# Badge.net
KiCad netlist of a schematic drawn in Altium Designer
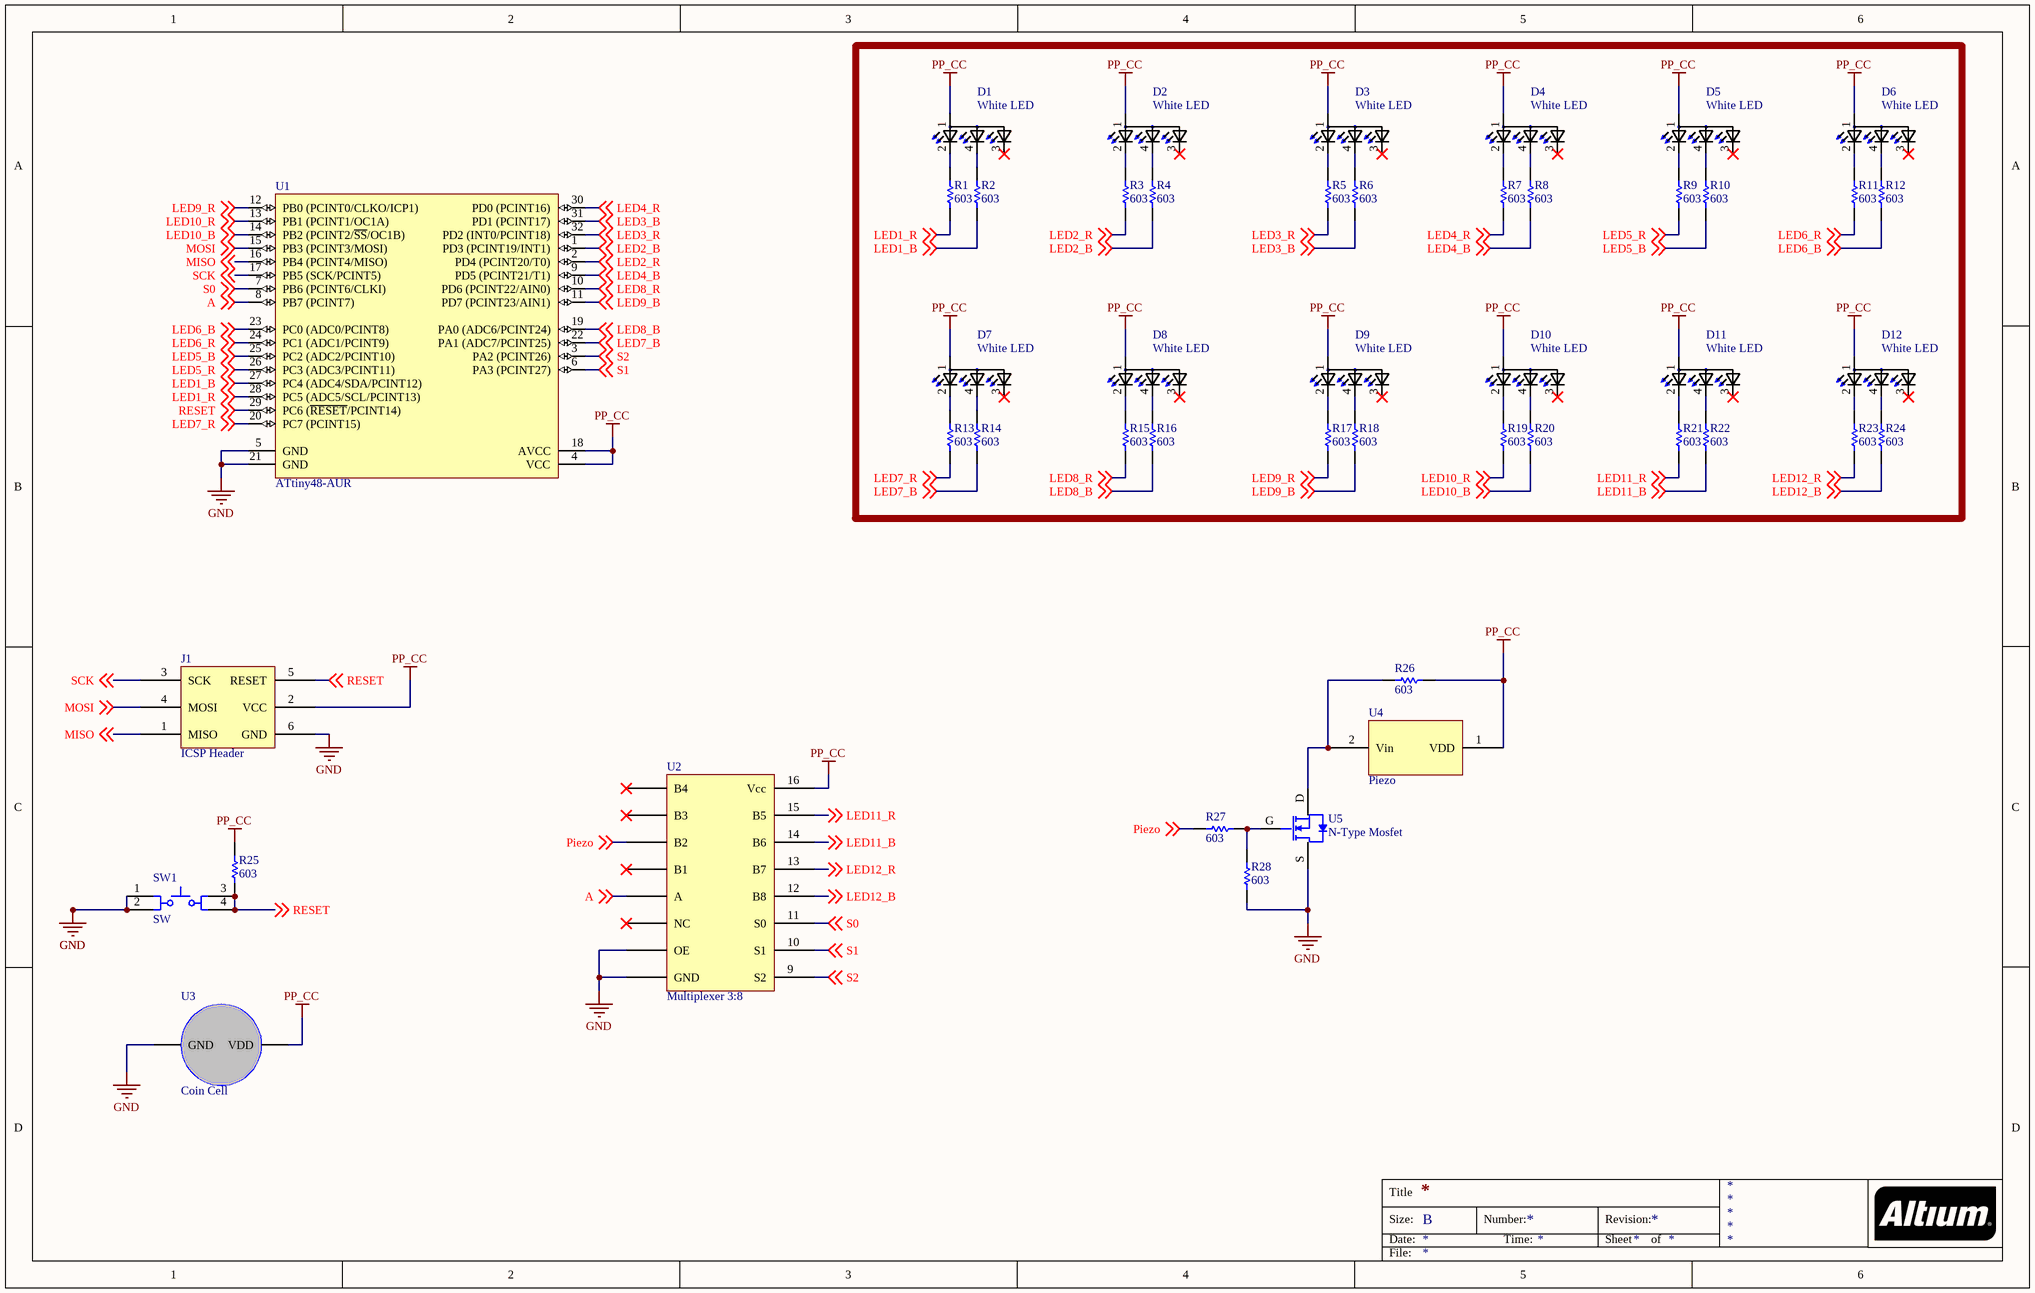
[diagram p0: Badge.SchDoc]

(export (version "E")
  (design (tool "Eeschema 10.0.6"))
  (components
    (comp (ref "D1")
      (value "White LED")
      (footprint "*LED_ASMB-KTF0-0A306")
      (description "2220 Tricolor PLCC4 Surface Mount LED")
      (fields (field (name "MF") "Broadcom Limited") (field (name "DIGI-KEY_PART_NUMBER") "516-3906-1-ND"))
      (libsource (lib "badge") (part "ASMB-KTF0-0A306"))
    )
    (comp (ref "D2")
      (value "White LED")
      (footprint "*LED_ASMB-KTF0-0A306")
      (description "2220 Tricolor PLCC4 Surface Mount LED")
      (fields (field (name "MF") "Broadcom Limited") (field (name "DIGI-KEY_PART_NUMBER") "516-3906-1-ND"))
      (libsource (lib "badge") (part "ASMB-KTF0-0A306"))
    )
    (comp (ref "D3")
      (value "White LED")
      (footprint "*LED_ASMB-KTF0-0A306")
      (description "2220 Tricolor PLCC4 Surface Mount LED")
      (fields (field (name "MF") "Broadcom Limited") (field (name "DIGI-KEY_PART_NUMBER") "516-3906-1-ND"))
      (libsource (lib "badge") (part "ASMB-KTF0-0A306"))
    )
    (comp (ref "D4")
      (value "White LED")
      (footprint "*LED_ASMB-KTF0-0A306")
      (description "2220 Tricolor PLCC4 Surface Mount LED")
      (fields (field (name "MF") "Broadcom Limited") (field (name "DIGI-KEY_PART_NUMBER") "516-3906-1-ND"))
      (libsource (lib "badge") (part "ASMB-KTF0-0A306"))
    )
    (comp (ref "D5")
      (value "White LED")
      (footprint "*LED_ASMB-KTF0-0A306")
      (description "2220 Tricolor PLCC4 Surface Mount LED")
      (fields (field (name "MF") "Broadcom Limited") (field (name "DIGI-KEY_PART_NUMBER") "516-3906-1-ND"))
      (libsource (lib "badge") (part "ASMB-KTF0-0A306"))
    )
    (comp (ref "D6")
      (value "White LED")
      (footprint "*LED_ASMB-KTF0-0A306")
      (description "2220 Tricolor PLCC4 Surface Mount LED")
      (fields (field (name "MF") "Broadcom Limited") (field (name "DIGI-KEY_PART_NUMBER") "516-3906-1-ND"))
      (libsource (lib "badge") (part "ASMB-KTF0-0A306"))
    )
    (comp (ref "D7")
      (value "White LED")
      (footprint "*LED_ASMB-KTF0-0A306")
      (description "2220 Tricolor PLCC4 Surface Mount LED")
      (fields (field (name "MF") "Broadcom Limited") (field (name "DIGI-KEY_PART_NUMBER") "516-3906-1-ND"))
      (libsource (lib "badge") (part "ASMB-KTF0-0A306"))
    )
    (comp (ref "D8")
      (value "White LED")
      (footprint "*LED_ASMB-KTF0-0A306")
      (description "2220 Tricolor PLCC4 Surface Mount LED")
      (fields (field (name "MF") "Broadcom Limited") (field (name "DIGI-KEY_PART_NUMBER") "516-3906-1-ND"))
      (libsource (lib "badge") (part "ASMB-KTF0-0A306"))
    )
    (comp (ref "D9")
      (value "White LED")
      (footprint "*LED_ASMB-KTF0-0A306")
      (description "2220 Tricolor PLCC4 Surface Mount LED")
      (fields (field (name "MF") "Broadcom Limited") (field (name "DIGI-KEY_PART_NUMBER") "516-3906-1-ND"))
      (libsource (lib "badge") (part "ASMB-KTF0-0A306"))
    )
    (comp (ref "D10")
      (value "White LED")
      (footprint "*LED_ASMB-KTF0-0A306")
      (description "2220 Tricolor PLCC4 Surface Mount LED")
      (fields (field (name "MF") "Broadcom Limited") (field (name "DIGI-KEY_PART_NUMBER") "516-3906-1-ND"))
      (libsource (lib "badge") (part "ASMB-KTF0-0A306"))
    )
    (comp (ref "D11")
      (value "White LED")
      (footprint "*LED_ASMB-KTF0-0A306")
      (description "2220 Tricolor PLCC4 Surface Mount LED")
      (fields (field (name "MF") "Broadcom Limited") (field (name "DIGI-KEY_PART_NUMBER") "516-3906-1-ND"))
      (libsource (lib "badge") (part "ASMB-KTF0-0A306"))
    )
    (comp (ref "D12")
      (value "White LED")
      (footprint "*LED_ASMB-KTF0-0A306")
      (description "2220 Tricolor PLCC4 Surface Mount LED")
      (fields (field (name "MF") "Broadcom Limited") (field (name "DIGI-KEY_PART_NUMBER") "516-3906-1-ND"))
      (libsource (lib "badge") (part "ASMB-KTF0-0A306"))
    )
    (comp (ref "J1")
      (value "ICSP Header")
      (footprint "programmer header")
      (libsource (lib "badge") (part "ICSP Header"))
    )
    (comp (ref "R1")
      (value "603")
      (footprint "RESC0603(1608)_L")
      (description "330R 0.1W 5% 0603 (1608 Metric)  SMD")
      (fields (field (name "TOLERANCE") "5 %") (field (name "POWER") "0.1 W"))
      (libsource (lib "Altium Content Vault") (part "RES"))
    )
    (comp (ref "R2")
      (value "603")
      (footprint "RESC0603(1608)_L")
      (description "330R 0.1W 5% 0603 (1608 Metric)  SMD")
      (fields (field (name "TOLERANCE") "5 %") (field (name "POWER") "0.1 W"))
      (libsource (lib "Altium Content Vault") (part "RES"))
    )
    (comp (ref "R3")
      (value "603")
      (footprint "RESC0603(1608)_L")
      (description "330R 0.1W 5% 0603 (1608 Metric)  SMD")
      (fields (field (name "TOLERANCE") "5 %") (field (name "POWER") "0.1 W"))
      (libsource (lib "Altium Content Vault") (part "RES"))
    )
    (comp (ref "R4")
      (value "603")
      (footprint "RESC0603(1608)_L")
      (description "330R 0.1W 5% 0603 (1608 Metric)  SMD")
      (fields (field (name "TOLERANCE") "5 %") (field (name "POWER") "0.1 W"))
      (libsource (lib "Altium Content Vault") (part "RES"))
    )
    (comp (ref "R5")
      (value "603")
      (footprint "RESC0603(1608)_L")
      (description "330R 0.1W 5% 0603 (1608 Metric)  SMD")
      (fields (field (name "TOLERANCE") "5 %") (field (name "POWER") "0.1 W"))
      (libsource (lib "Altium Content Vault") (part "RES"))
    )
    (comp (ref "R6")
      (value "603")
      (footprint "RESC0603(1608)_L")
      (description "330R 0.1W 5% 0603 (1608 Metric)  SMD")
      (fields (field (name "TOLERANCE") "5 %") (field (name "POWER") "0.1 W"))
      (libsource (lib "Altium Content Vault") (part "RES"))
    )
    (comp (ref "R7")
      (value "603")
      (footprint "RESC0603(1608)_L")
      (description "330R 0.1W 5% 0603 (1608 Metric)  SMD")
      (fields (field (name "TOLERANCE") "5 %") (field (name "POWER") "0.1 W"))
      (libsource (lib "Altium Content Vault") (part "RES"))
    )
    (comp (ref "R8")
      (value "603")
      (footprint "RESC0603(1608)_L")
      (description "330R 0.1W 5% 0603 (1608 Metric)  SMD")
      (fields (field (name "TOLERANCE") "5 %") (field (name "POWER") "0.1 W"))
      (libsource (lib "Altium Content Vault") (part "RES"))
    )
    (comp (ref "R9")
      (value "603")
      (footprint "RESC0603(1608)_L")
      (description "330R 0.1W 5% 0603 (1608 Metric)  SMD")
      (fields (field (name "TOLERANCE") "5 %") (field (name "POWER") "0.1 W"))
      (libsource (lib "Altium Content Vault") (part "RES"))
    )
    (comp (ref "R10")
      (value "603")
      (footprint "RESC0603(1608)_L")
      (description "330R 0.1W 5% 0603 (1608 Metric)  SMD")
      (fields (field (name "TOLERANCE") "5 %") (field (name "POWER") "0.1 W"))
      (libsource (lib "Altium Content Vault") (part "RES"))
    )
    (comp (ref "R11")
      (value "603")
      (footprint "RESC0603(1608)_L")
      (description "330R 0.1W 5% 0603 (1608 Metric)  SMD")
      (fields (field (name "TOLERANCE") "5 %") (field (name "POWER") "0.1 W"))
      (libsource (lib "Altium Content Vault") (part "RES"))
    )
    (comp (ref "R12")
      (value "603")
      (footprint "RESC0603(1608)_L")
      (description "330R 0.1W 5% 0603 (1608 Metric)  SMD")
      (fields (field (name "TOLERANCE") "5 %") (field (name "POWER") "0.1 W"))
      (libsource (lib "Altium Content Vault") (part "RES"))
    )
    (comp (ref "R13")
      (value "603")
      (footprint "RESC0603(1608)_L")
      (description "330R 0.1W 5% 0603 (1608 Metric)  SMD")
      (fields (field (name "TOLERANCE") "5 %") (field (name "POWER") "0.1 W"))
      (libsource (lib "Altium Content Vault") (part "RES"))
    )
    (comp (ref "R14")
      (value "603")
      (footprint "RESC0603(1608)_L")
      (description "330R 0.1W 5% 0603 (1608 Metric)  SMD")
      (fields (field (name "TOLERANCE") "5 %") (field (name "POWER") "0.1 W"))
      (libsource (lib "Altium Content Vault") (part "RES"))
    )
    (comp (ref "R15")
      (value "603")
      (footprint "RESC0603(1608)_L")
      (description "330R 0.1W 5% 0603 (1608 Metric)  SMD")
      (fields (field (name "TOLERANCE") "5 %") (field (name "POWER") "0.1 W"))
      (libsource (lib "Altium Content Vault") (part "RES"))
    )
    (comp (ref "R16")
      (value "603")
      (footprint "RESC0603(1608)_L")
      (description "330R 0.1W 5% 0603 (1608 Metric)  SMD")
      (fields (field (name "TOLERANCE") "5 %") (field (name "POWER") "0.1 W"))
      (libsource (lib "Altium Content Vault") (part "RES"))
    )
    (comp (ref "R17")
      (value "603")
      (footprint "RESC0603(1608)_L")
      (description "330R 0.1W 5% 0603 (1608 Metric)  SMD")
      (fields (field (name "TOLERANCE") "5 %") (field (name "POWER") "0.1 W"))
      (libsource (lib "Altium Content Vault") (part "RES"))
    )
    (comp (ref "R18")
      (value "603")
      (footprint "RESC0603(1608)_L")
      (description "330R 0.1W 5% 0603 (1608 Metric)  SMD")
      (fields (field (name "TOLERANCE") "5 %") (field (name "POWER") "0.1 W"))
      (libsource (lib "Altium Content Vault") (part "RES"))
    )
    (comp (ref "R19")
      (value "603")
      (footprint "RESC0603(1608)_L")
      (description "330R 0.1W 5% 0603 (1608 Metric)  SMD")
      (fields (field (name "TOLERANCE") "5 %") (field (name "POWER") "0.1 W"))
      (libsource (lib "Altium Content Vault") (part "RES"))
    )
    (comp (ref "R20")
      (value "603")
      (footprint "RESC0603(1608)_L")
      (description "330R 0.1W 5% 0603 (1608 Metric)  SMD")
      (fields (field (name "TOLERANCE") "5 %") (field (name "POWER") "0.1 W"))
      (libsource (lib "Altium Content Vault") (part "RES"))
    )
    (comp (ref "R21")
      (value "603")
      (footprint "RESC0603(1608)_L")
      (description "330R 0.1W 5% 0603 (1608 Metric)  SMD")
      (fields (field (name "TOLERANCE") "5 %") (field (name "POWER") "0.1 W"))
      (libsource (lib "Altium Content Vault") (part "RES"))
    )
    (comp (ref "R22")
      (value "603")
      (footprint "RESC0603(1608)_L")
      (description "330R 0.1W 5% 0603 (1608 Metric)  SMD")
      (fields (field (name "TOLERANCE") "5 %") (field (name "POWER") "0.1 W"))
      (libsource (lib "Altium Content Vault") (part "RES"))
    )
    (comp (ref "R23")
      (value "603")
      (footprint "RESC0603(1608)_L")
      (description "330R 0.1W 5% 0603 (1608 Metric)  SMD")
      (fields (field (name "TOLERANCE") "5 %") (field (name "POWER") "0.1 W"))
      (libsource (lib "Altium Content Vault") (part "RES"))
    )
    (comp (ref "R24")
      (value "603")
      (footprint "RESC0603(1608)_L")
      (description "330R 0.1W 5% 0603 (1608 Metric)  SMD")
      (fields (field (name "TOLERANCE") "5 %") (field (name "POWER") "0.1 W"))
      (libsource (lib "Altium Content Vault") (part "RES"))
    )
    (comp (ref "R25")
      (value "603")
      (footprint "RESC1608X50X30LL20T20")
      (fields (field (name "MPN") "RR0816P-103-D") (field (name "MANUFACTURER") "Susumu"))
      (libsource (lib "Altium Content Vault") (part "RES"))
    )
    (comp (ref "R26")
      (value "603")
      (footprint "RESC1608X50X30LL20T20")
      (fields (field (name "MPN") "RR0816P-103-D") (field (name "MANUFACTURER") "Susumu"))
      (libsource (lib "Altium Content Vault") (part "RES"))
    )
    (comp (ref "R27")
      (value "603")
      (footprint "RESC1608X50X30LL20T20")
      (fields (field (name "MPN") "RR0816P-103-D") (field (name "MANUFACTURER") "Susumu"))
      (libsource (lib "Altium Content Vault") (part "RES"))
    )
    (comp (ref "R28")
      (value "603")
      (footprint "RESC1608X50X30LL20T20")
      (fields (field (name "MPN") "RR0816P-103-D") (field (name "MANUFACTURER") "Susumu"))
      (libsource (lib "Altium Content Vault") (part "RES"))
    )
    (comp (ref "SW1")
      (value "SW")
      (footprint "CKCP-PTS645S_V")
      (description "Tact Switch, SPST-NO, 50 mA, -20 to 60 degC, 4-Pin SMD, RoHS, Tape and Reel")
      (fields (field (name "MPN") "PTS645S") (field (name "MANUFACTURER") "C&K Components"))
      (libsource (lib "Altium Content Vault") (part "SW-SPST-NO-4"))
    )
    (comp (ref "U1")
      (value "ATtiny48-AUR")
      (footprint "32A_N")
      (libsource (lib "Altium Content Vault") (part "MC-8B-ATT48-SQ32"))
    )
    (comp (ref "U2")
      (value "Multiplexer 3:8")
      (footprint "Multiplexer")
      (description "IC LV FET MUX/DEMUX 16-TSSOP")
      (fields (field (name "MANUFACTURER") "TI") (field (name "MPN") "SN74CBTLV3251PWR"))
      (libsource (lib "badge") (part "Multiplexer"))
    )
    (comp (ref "U3")
      (value "Coin Cell")
      (footprint "Batt")
      (description "Battery Retainer Coin, 20.0mm 1 Cell SMD (SMT) Tab")
      (fields (field (name "MPN") "3034TR") (field (name "MANUFACTURER") "Keystone Electronics"))
      (libsource (lib "badge") (part "Batt"))
    )
    (comp (ref "U4")
      (value "Piezo")
      (footprint "Piezo")
      (description "AUDIO PIEZO TRANSDUCER 30V TH")
      (fields (field (name "MPN") "PS1240P02BT") (field (name "MANUFACTURER") "TDK Corporation"))
      (libsource (lib "badge") (part "Piezo"))
    )
    (comp (ref "U5")
      (value "N-Type Mosfet")
      (footprint "2N7002K-7")
      (description "N-Channel 800V 1A (Tc) 45W (Tc) Surface Mount D-Pak")
      (fields (field (name "MPN") "2N7002K-7") (field (name "MANUFACTURER") "Diodes Incorporated"))
      (libsource (lib "badge") (part "2N7002K-7"))
    )
  )
  (nets
    (net (code "1") (name "A") (class "Default")
      (node (ref "U1") (pin "8") (pinfunction "PB7_(PCINT7)_8") (pintype "bidirectional"))
      (node (ref "U2") (pin "5") (pinfunction "A_5") (pintype "passive"))
    )
    (net (code "2") (name "GND") (class "Default")
      (node (ref "J1") (pin "6") (pinfunction "GND_6") (pintype "passive"))
      (node (ref "R28") (pin "2") (pinfunction "2_2") (pintype "passive"))
      (node (ref "SW1") (pin "1") (pinfunction "1_1") (pintype "passive"))
      (node (ref "SW1") (pin "2") (pinfunction "2_2") (pintype "passive"))
      (node (ref "U1") (pin "21") (pinfunction "GND_21") (pintype "power_in"))
      (node (ref "U1") (pin "5") (pinfunction "GND_5") (pintype "power_in"))
      (node (ref "U2") (pin "7") (pinfunction "OE_7") (pintype "passive"))
      (node (ref "U2") (pin "8") (pinfunction "GND_8") (pintype "passive"))
      (node (ref "U3") (pin "GND") (pinfunction "GND_GND") (pintype "passive"))
      (node (ref "U5") (pin "S") (pinfunction "SOURCE_S") (pintype "passive"))
    )
    (net (code "3") (name "LED1_B") (class "Default")
      (node (ref "R2") (pin "1") (pinfunction "1_1") (pintype "passive"))
      (node (ref "U1") (pin "27") (pinfunction "PC4_(ADC4/SDA/PCINT12)_27") (pintype "bidirectional"))
    )
    (net (code "4") (name "LED1_R") (class "Default")
      (node (ref "R1") (pin "1") (pinfunction "1_1") (pintype "passive"))
      (node (ref "U1") (pin "28") (pinfunction "PC5_(ADC5/SCL/PCINT13)_28") (pintype "bidirectional"))
    )
    (net (code "5") (name "LED2_B") (class "Default")
      (node (ref "R4") (pin "1") (pinfunction "1_1") (pintype "passive"))
      (node (ref "U1") (pin "1") (pinfunction "PD3_(PCINT19/INT1)_1") (pintype "bidirectional"))
    )
    (net (code "6") (name "LED2_R") (class "Default")
      (node (ref "R3") (pin "1") (pinfunction "1_1") (pintype "passive"))
      (node (ref "U1") (pin "2") (pinfunction "PD4_(PCINT20/T0)_2") (pintype "bidirectional"))
    )
    (net (code "7") (name "LED3_B") (class "Default")
      (node (ref "R6") (pin "1") (pinfunction "1_1") (pintype "passive"))
      (node (ref "U1") (pin "31") (pinfunction "PD1_(PCINT17)_31") (pintype "bidirectional"))
    )
    (net (code "8") (name "LED3_R") (class "Default")
      (node (ref "R5") (pin "1") (pinfunction "1_1") (pintype "passive"))
      (node (ref "U1") (pin "32") (pinfunction "PD2_(INT0/PCINT18)_32") (pintype "bidirectional"))
    )
    (net (code "9") (name "LED4_B") (class "Default")
      (node (ref "R8") (pin "1") (pinfunction "1_1") (pintype "passive"))
      (node (ref "U1") (pin "9") (pinfunction "PD5_(PCINT21/T1)_9") (pintype "bidirectional"))
    )
    (net (code "10") (name "LED4_R") (class "Default")
      (node (ref "R7") (pin "1") (pinfunction "1_1") (pintype "passive"))
      (node (ref "U1") (pin "30") (pinfunction "PD0_(PCINT16)_30") (pintype "bidirectional"))
    )
    (net (code "11") (name "LED5_B") (class "Default")
      (node (ref "R10") (pin "1") (pinfunction "1_1") (pintype "passive"))
      (node (ref "U1") (pin "25") (pinfunction "PC2_(ADC2/PCINT10)_25") (pintype "bidirectional"))
    )
    (net (code "12") (name "LED5_R") (class "Default")
      (node (ref "R9") (pin "1") (pinfunction "1_1") (pintype "passive"))
      (node (ref "U1") (pin "26") (pinfunction "PC3_(ADC3/PCINT11)_26") (pintype "bidirectional"))
    )
    (net (code "13") (name "LED6_B") (class "Default")
      (node (ref "R12") (pin "1") (pinfunction "1_1") (pintype "passive"))
      (node (ref "U1") (pin "23") (pinfunction "PC0_(ADC0/PCINT8)_23") (pintype "bidirectional"))
    )
    (net (code "14") (name "LED6_R") (class "Default")
      (node (ref "R11") (pin "1") (pinfunction "1_1") (pintype "passive"))
      (node (ref "U1") (pin "24") (pinfunction "PC1_(ADC1/PCINT9)_24") (pintype "bidirectional"))
    )
    (net (code "15") (name "LED7_B") (class "Default")
      (node (ref "R14") (pin "1") (pinfunction "1_1") (pintype "passive"))
      (node (ref "U1") (pin "22") (pinfunction "PA1_(ADC7/PCINT25)_22") (pintype "bidirectional"))
    )
    (net (code "16") (name "LED7_R") (class "Default")
      (node (ref "R13") (pin "1") (pinfunction "1_1") (pintype "passive"))
      (node (ref "U1") (pin "20") (pinfunction "PC7_(PCINT15)_20") (pintype "bidirectional"))
    )
    (net (code "17") (name "LED8_B") (class "Default")
      (node (ref "R16") (pin "1") (pinfunction "1_1") (pintype "passive"))
      (node (ref "U1") (pin "19") (pinfunction "PA0_(ADC6/PCINT24)_19") (pintype "bidirectional"))
    )
    (net (code "18") (name "LED8_R") (class "Default")
      (node (ref "R15") (pin "1") (pinfunction "1_1") (pintype "passive"))
      (node (ref "U1") (pin "10") (pinfunction "PD6_(PCINT22/AIN0)_10") (pintype "bidirectional"))
    )
    (net (code "19") (name "LED9_B") (class "Default")
      (node (ref "R18") (pin "1") (pinfunction "1_1") (pintype "passive"))
      (node (ref "U1") (pin "11") (pinfunction "PD7_(PCINT23/AIN1)_11") (pintype "bidirectional"))
    )
    (net (code "20") (name "LED9_R") (class "Default")
      (node (ref "R17") (pin "1") (pinfunction "1_1") (pintype "passive"))
      (node (ref "U1") (pin "12") (pinfunction "PB0_(PCINT0/CLKO/ICP1)_12") (pintype "bidirectional"))
    )
    (net (code "21") (name "LED10_B") (class "Default")
      (node (ref "R20") (pin "1") (pinfunction "1_1") (pintype "passive"))
      (node (ref "U1") (pin "14") (pinfunction "PB2_(PCINT2/~{SS}/OC1B)_14") (pintype "bidirectional"))
    )
    (net (code "22") (name "LED10_R") (class "Default")
      (node (ref "R19") (pin "1") (pinfunction "1_1") (pintype "passive"))
      (node (ref "U1") (pin "13") (pinfunction "PB1_(PCINT1/OC1A)_13") (pintype "bidirectional"))
    )
    (net (code "23") (name "LED11_B") (class "Default")
      (node (ref "R22") (pin "1") (pinfunction "1_1") (pintype "passive"))
      (node (ref "U2") (pin "14") (pinfunction "B6_14") (pintype "passive"))
    )
    (net (code "24") (name "LED11_R") (class "Default")
      (node (ref "R21") (pin "1") (pinfunction "1_1") (pintype "passive"))
      (node (ref "U2") (pin "15") (pinfunction "B5_15") (pintype "passive"))
    )
    (net (code "25") (name "LED12_B") (class "Default")
      (node (ref "R24") (pin "1") (pinfunction "1_1") (pintype "passive"))
      (node (ref "U2") (pin "12") (pinfunction "B8_12") (pintype "passive"))
    )
    (net (code "26") (name "LED12_R") (class "Default")
      (node (ref "R23") (pin "1") (pinfunction "1_1") (pintype "passive"))
      (node (ref "U2") (pin "13") (pinfunction "B7_13") (pintype "passive"))
    )
    (net (code "27") (name "MISO") (class "Default")
      (node (ref "J1") (pin "1") (pinfunction "MISO_1") (pintype "passive"))
      (node (ref "U1") (pin "16") (pinfunction "PB4_(PCINT4/MISO)_16") (pintype "bidirectional"))
    )
    (net (code "28") (name "MOSI") (class "Default")
      (node (ref "J1") (pin "4") (pinfunction "MOSI_4") (pintype "passive"))
      (node (ref "U1") (pin "15") (pinfunction "PB3_(PCINT3/MOSI)_15") (pintype "bidirectional"))
    )
    (net (code "29") (name "Net-(D1-CBLUE)") (class "Default")
      (node (ref "D1") (pin "4") (pinfunction "CBLUE_4") (pintype "passive"))
      (node (ref "R2") (pin "2") (pinfunction "2_2") (pintype "passive"))
    )
    (net (code "30") (name "Net-(D1-CRED)") (class "Default")
      (node (ref "D1") (pin "2") (pinfunction "CRED_2") (pintype "passive"))
      (node (ref "R1") (pin "2") (pinfunction "2_2") (pintype "passive"))
    )
    (net (code "31") (name "Net-(D2-CBLUE)") (class "Default")
      (node (ref "D2") (pin "4") (pinfunction "CBLUE_4") (pintype "passive"))
      (node (ref "R4") (pin "2") (pinfunction "2_2") (pintype "passive"))
    )
    (net (code "32") (name "Net-(D2-CRED)") (class "Default")
      (node (ref "D2") (pin "2") (pinfunction "CRED_2") (pintype "passive"))
      (node (ref "R3") (pin "2") (pinfunction "2_2") (pintype "passive"))
    )
    (net (code "33") (name "Net-(D3-CBLUE)") (class "Default")
      (node (ref "D3") (pin "4") (pinfunction "CBLUE_4") (pintype "passive"))
      (node (ref "R6") (pin "2") (pinfunction "2_2") (pintype "passive"))
    )
    (net (code "34") (name "Net-(D3-CRED)") (class "Default")
      (node (ref "D3") (pin "2") (pinfunction "CRED_2") (pintype "passive"))
      (node (ref "R5") (pin "2") (pinfunction "2_2") (pintype "passive"))
    )
    (net (code "35") (name "Net-(D4-CBLUE)") (class "Default")
      (node (ref "D4") (pin "4") (pinfunction "CBLUE_4") (pintype "passive"))
      (node (ref "R8") (pin "2") (pinfunction "2_2") (pintype "passive"))
    )
    (net (code "36") (name "Net-(D4-CRED)") (class "Default")
      (node (ref "D4") (pin "2") (pinfunction "CRED_2") (pintype "passive"))
      (node (ref "R7") (pin "2") (pinfunction "2_2") (pintype "passive"))
    )
    (net (code "37") (name "Net-(D5-CBLUE)") (class "Default")
      (node (ref "D5") (pin "4") (pinfunction "CBLUE_4") (pintype "passive"))
      (node (ref "R10") (pin "2") (pinfunction "2_2") (pintype "passive"))
    )
    (net (code "38") (name "Net-(D5-CRED)") (class "Default")
      (node (ref "D5") (pin "2") (pinfunction "CRED_2") (pintype "passive"))
      (node (ref "R9") (pin "2") (pinfunction "2_2") (pintype "passive"))
    )
    (net (code "39") (name "Net-(D6-CBLUE)") (class "Default")
      (node (ref "D6") (pin "4") (pinfunction "CBLUE_4") (pintype "passive"))
      (node (ref "R12") (pin "2") (pinfunction "2_2") (pintype "passive"))
    )
    (net (code "40") (name "Net-(D6-CRED)") (class "Default")
      (node (ref "D6") (pin "2") (pinfunction "CRED_2") (pintype "passive"))
      (node (ref "R11") (pin "2") (pinfunction "2_2") (pintype "passive"))
    )
    (net (code "41") (name "Net-(D7-CBLUE)") (class "Default")
      (node (ref "D7") (pin "4") (pinfunction "CBLUE_4") (pintype "passive"))
      (node (ref "R14") (pin "2") (pinfunction "2_2") (pintype "passive"))
    )
    (net (code "42") (name "Net-(D7-CRED)") (class "Default")
      (node (ref "D7") (pin "2") (pinfunction "CRED_2") (pintype "passive"))
      (node (ref "R13") (pin "2") (pinfunction "2_2") (pintype "passive"))
    )
    (net (code "43") (name "Net-(D8-CBLUE)") (class "Default")
      (node (ref "D8") (pin "4") (pinfunction "CBLUE_4") (pintype "passive"))
      (node (ref "R16") (pin "2") (pinfunction "2_2") (pintype "passive"))
    )
    (net (code "44") (name "Net-(D8-CRED)") (class "Default")
      (node (ref "D8") (pin "2") (pinfunction "CRED_2") (pintype "passive"))
      (node (ref "R15") (pin "2") (pinfunction "2_2") (pintype "passive"))
    )
    (net (code "45") (name "Net-(D9-CBLUE)") (class "Default")
      (node (ref "D9") (pin "4") (pinfunction "CBLUE_4") (pintype "passive"))
      (node (ref "R18") (pin "2") (pinfunction "2_2") (pintype "passive"))
    )
    (net (code "46") (name "Net-(D9-CRED)") (class "Default")
      (node (ref "D9") (pin "2") (pinfunction "CRED_2") (pintype "passive"))
      (node (ref "R17") (pin "2") (pinfunction "2_2") (pintype "passive"))
    )
    (net (code "47") (name "Net-(D10-CBLUE)") (class "Default")
      (node (ref "D10") (pin "4") (pinfunction "CBLUE_4") (pintype "passive"))
      (node (ref "R20") (pin "2") (pinfunction "2_2") (pintype "passive"))
    )
    (net (code "48") (name "Net-(D10-CRED)") (class "Default")
      (node (ref "D10") (pin "2") (pinfunction "CRED_2") (pintype "passive"))
      (node (ref "R19") (pin "2") (pinfunction "2_2") (pintype "passive"))
    )
    (net (code "49") (name "Net-(D11-CBLUE)") (class "Default")
      (node (ref "D11") (pin "4") (pinfunction "CBLUE_4") (pintype "passive"))
      (node (ref "R22") (pin "2") (pinfunction "2_2") (pintype "passive"))
    )
    (net (code "50") (name "Net-(D11-CRED)") (class "Default")
      (node (ref "D11") (pin "2") (pinfunction "CRED_2") (pintype "passive"))
      (node (ref "R21") (pin "2") (pinfunction "2_2") (pintype "passive"))
    )
    (net (code "51") (name "Net-(D12-CBLUE)") (class "Default")
      (node (ref "D12") (pin "4") (pinfunction "CBLUE_4") (pintype "passive"))
      (node (ref "R24") (pin "2") (pinfunction "2_2") (pintype "passive"))
    )
    (net (code "52") (name "Net-(D12-CRED)") (class "Default")
      (node (ref "D12") (pin "2") (pinfunction "CRED_2") (pintype "passive"))
      (node (ref "R23") (pin "2") (pinfunction "2_2") (pintype "passive"))
    )
    (net (code "53") (name "Net-(U4-Vin)") (class "Default")
      (node (ref "R26") (pin "2") (pinfunction "2_2") (pintype "passive"))
      (node (ref "U4") (pin "2") (pinfunction "Vin_2") (pintype "passive"))
      (node (ref "U5") (pin "D") (pinfunction "DRAIN_D") (pintype "passive"))
    )
    (net (code "54") (name "Net-(U5-GATE)") (class "Default")
      (node (ref "R27") (pin "1") (pinfunction "1_1") (pintype "passive"))
      (node (ref "R28") (pin "1") (pinfunction "1_1") (pintype "passive"))
      (node (ref "U5") (pin "G") (pinfunction "GATE_G") (pintype "passive"))
    )
    (net (code "55") (name "PP_CC") (class "Default")
      (node (ref "D1") (pin "1") (pinfunction "A_1") (pintype "passive"))
      (node (ref "D10") (pin "1") (pinfunction "A_1") (pintype "passive"))
      (node (ref "D11") (pin "1") (pinfunction "A_1") (pintype "passive"))
      (node (ref "D12") (pin "1") (pinfunction "A_1") (pintype "passive"))
      (node (ref "D2") (pin "1") (pinfunction "A_1") (pintype "passive"))
      (node (ref "D3") (pin "1") (pinfunction "A_1") (pintype "passive"))
      (node (ref "D4") (pin "1") (pinfunction "A_1") (pintype "passive"))
      (node (ref "D5") (pin "1") (pinfunction "A_1") (pintype "passive"))
      (node (ref "D6") (pin "1") (pinfunction "A_1") (pintype "passive"))
      (node (ref "D7") (pin "1") (pinfunction "A_1") (pintype "passive"))
      (node (ref "D8") (pin "1") (pinfunction "A_1") (pintype "passive"))
      (node (ref "D9") (pin "1") (pinfunction "A_1") (pintype "passive"))
      (node (ref "J1") (pin "2") (pinfunction "VCC_2") (pintype "passive"))
      (node (ref "R25") (pin "2") (pinfunction "2_2") (pintype "passive"))
      (node (ref "R26") (pin "1") (pinfunction "1_1") (pintype "passive"))
      (node (ref "U1") (pin "18") (pinfunction "AVCC_18") (pintype "power_in"))
      (node (ref "U1") (pin "4") (pinfunction "VCC_4") (pintype "power_in"))
      (node (ref "U2") (pin "16") (pinfunction "Vcc_16") (pintype "passive"))
      (node (ref "U3") (pin "VDD") (pinfunction "VDD_VDD") (pintype "passive"))
      (node (ref "U4") (pin "1") (pinfunction "VDD_1") (pintype "passive"))
    )
    (net (code "56") (name "Piezo") (class "Default")
      (node (ref "R27") (pin "2") (pinfunction "2_2") (pintype "passive"))
      (node (ref "U2") (pin "3") (pinfunction "B2_3") (pintype "passive"))
    )
    (net (code "57") (name "RESET") (class "Default")
      (node (ref "J1") (pin "5") (pinfunction "RESET_5") (pintype "passive"))
      (node (ref "R25") (pin "1") (pinfunction "1_1") (pintype "passive"))
      (node (ref "SW1") (pin "3") (pinfunction "3_3") (pintype "passive"))
      (node (ref "SW1") (pin "4") (pinfunction "4_4") (pintype "passive"))
      (node (ref "U1") (pin "29") (pinfunction "PC6_(~{RESET}/PCINT14)_29") (pintype "bidirectional"))
    )
    (net (code "58") (name "S0") (class "Default")
      (node (ref "U1") (pin "7") (pinfunction "PB6_(PCINT6/CLKI)_7") (pintype "bidirectional"))
      (node (ref "U2") (pin "11") (pinfunction "S0_11") (pintype "passive"))
    )
    (net (code "59") (name "S1") (class "Default")
      (node (ref "U1") (pin "6") (pinfunction "PA3_(PCINT27)_6") (pintype "bidirectional"))
      (node (ref "U2") (pin "10") (pinfunction "S1_10") (pintype "passive"))
    )
    (net (code "60") (name "S2") (class "Default")
      (node (ref "U1") (pin "3") (pinfunction "PA2_(PCINT26)_3") (pintype "bidirectional"))
      (node (ref "U2") (pin "9") (pinfunction "S2_9") (pintype "passive"))
    )
    (net (code "61") (name "SCK") (class "Default")
      (node (ref "J1") (pin "3") (pinfunction "SCK_3") (pintype "passive"))
      (node (ref "U1") (pin "17") (pinfunction "PB5_(SCK/PCINT5)_17") (pintype "bidirectional"))
    )
    (net (code "62") (name "unconnected-(D1-CGREEN-Pad3)") (class "Default")
      (node (ref "D1") (pin "3") (pinfunction "CGREEN_3") (pintype "passive+no_connect"))
    )
    (net (code "63") (name "unconnected-(D2-CGREEN-Pad3)") (class "Default")
      (node (ref "D2") (pin "3") (pinfunction "CGREEN_3") (pintype "passive+no_connect"))
    )
    (net (code "64") (name "unconnected-(D3-CGREEN-Pad3)") (class "Default")
      (node (ref "D3") (pin "3") (pinfunction "CGREEN_3") (pintype "passive+no_connect"))
    )
    (net (code "65") (name "unconnected-(D4-CGREEN-Pad3)") (class "Default")
      (node (ref "D4") (pin "3") (pinfunction "CGREEN_3") (pintype "passive+no_connect"))
    )
    (net (code "66") (name "unconnected-(D5-CGREEN-Pad3)") (class "Default")
      (node (ref "D5") (pin "3") (pinfunction "CGREEN_3") (pintype "passive+no_connect"))
    )
    (net (code "67") (name "unconnected-(D6-CGREEN-Pad3)") (class "Default")
      (node (ref "D6") (pin "3") (pinfunction "CGREEN_3") (pintype "passive+no_connect"))
    )
    (net (code "68") (name "unconnected-(D7-CGREEN-Pad3)") (class "Default")
      (node (ref "D7") (pin "3") (pinfunction "CGREEN_3") (pintype "passive+no_connect"))
    )
    (net (code "69") (name "unconnected-(D8-CGREEN-Pad3)") (class "Default")
      (node (ref "D8") (pin "3") (pinfunction "CGREEN_3") (pintype "passive+no_connect"))
    )
    (net (code "70") (name "unconnected-(D9-CGREEN-Pad3)") (class "Default")
      (node (ref "D9") (pin "3") (pinfunction "CGREEN_3") (pintype "passive+no_connect"))
    )
    (net (code "71") (name "unconnected-(D10-CGREEN-Pad3)") (class "Default")
      (node (ref "D10") (pin "3") (pinfunction "CGREEN_3") (pintype "passive+no_connect"))
    )
    (net (code "72") (name "unconnected-(D11-CGREEN-Pad3)") (class "Default")
      (node (ref "D11") (pin "3") (pinfunction "CGREEN_3") (pintype "passive+no_connect"))
    )
    (net (code "73") (name "unconnected-(D12-CGREEN-Pad3)") (class "Default")
      (node (ref "D12") (pin "3") (pinfunction "CGREEN_3") (pintype "passive+no_connect"))
    )
    (net (code "74") (name "unconnected-(U2-B1-Pad4)") (class "Default")
      (node (ref "U2") (pin "4") (pinfunction "B1_4") (pintype "passive+no_connect"))
    )
    (net (code "75") (name "unconnected-(U2-B3-Pad2)") (class "Default")
      (node (ref "U2") (pin "2") (pinfunction "B3_2") (pintype "passive+no_connect"))
    )
    (net (code "76") (name "unconnected-(U2-B4-Pad1)") (class "Default")
      (node (ref "U2") (pin "1") (pinfunction "B4_1") (pintype "passive+no_connect"))
    )
    (net (code "77") (name "unconnected-(U2-NC-Pad6)") (class "Default")
      (node (ref "U2") (pin "6") (pinfunction "NC_6") (pintype "passive+no_connect"))
    )
  )
)
